# msp430.net
KiCad netlist of a schematic drawn in Altium Designer
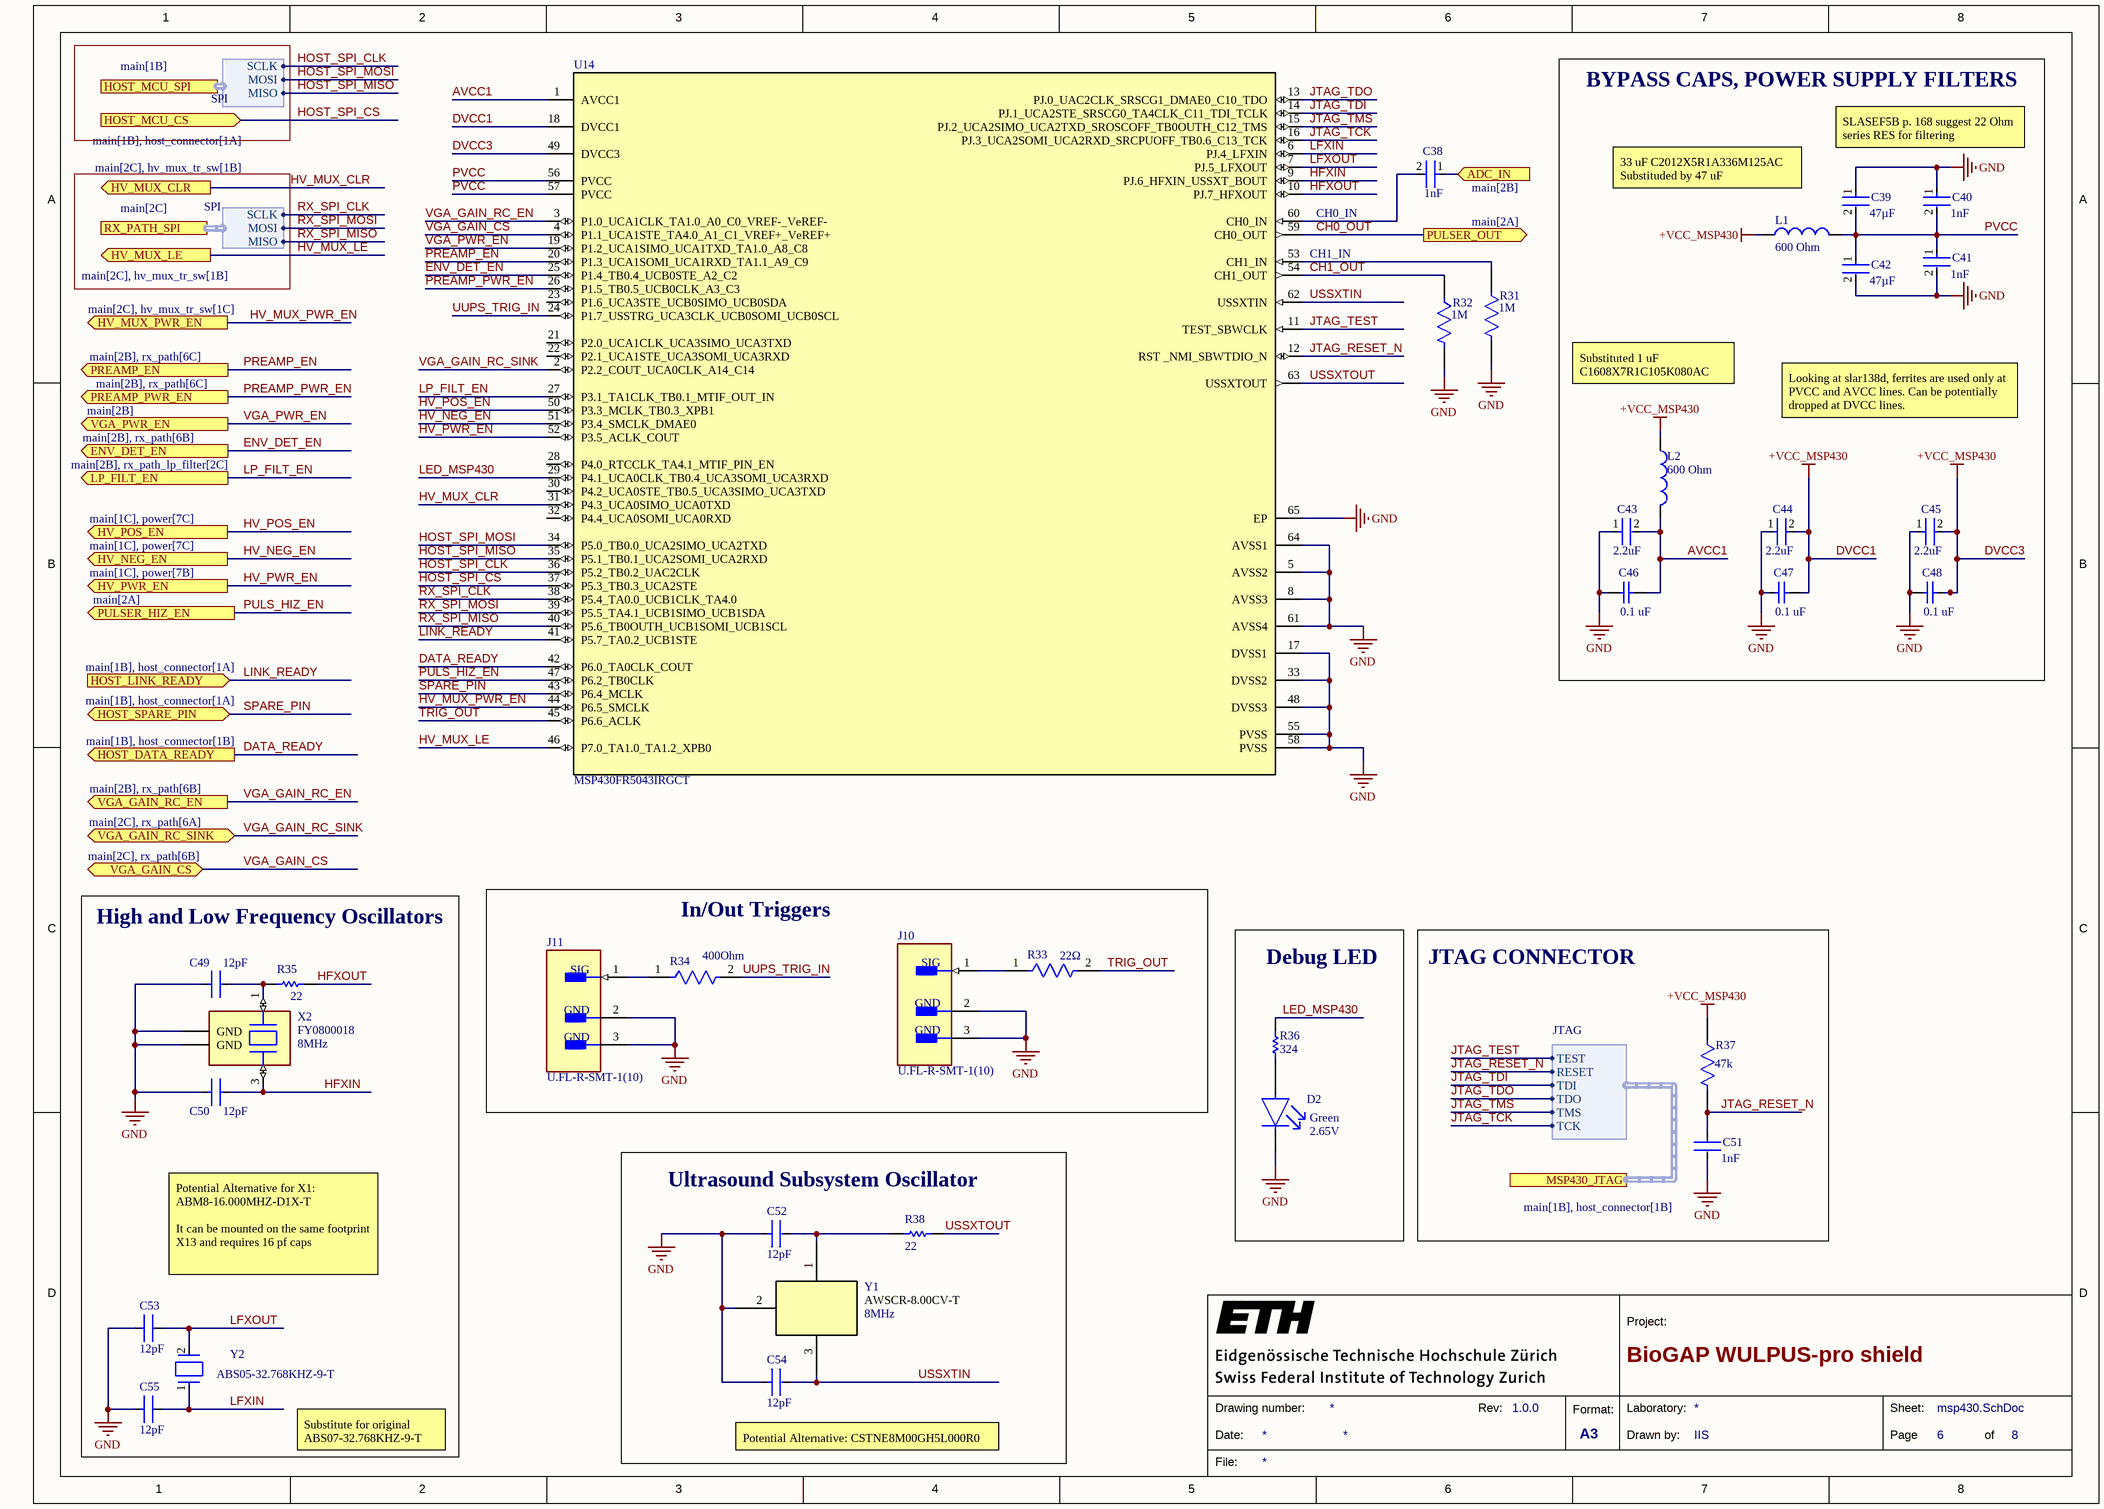
[diagram p0: msp430.SchDoc]

(export (version "E")
  (design (tool "Eeschema 10.0.6"))
  (components
    (comp (ref "C38")
      (value "GRM1555C1H102JA01D")
      (footprint "FP-GRM155-0_05-IPC_B")
      (fields
        (field (name "TOLERANCE") "5%")
        (field (name "VOLTAGE") "50V")
        (field (name "CAPACITANCE") "1nF")
      )
      (libsource (lib "") (part "02cd4be3c70576c341d710602a673aa_1"))
    )
    (comp (ref "C39")
      (value "GRM188R60J476ME01D")
      (footprint "FP-GRM188-0_2-MFG")
      (fields (field (name "TOLERANCE") "20%") (field (name "CAPACITANCE") "47µF"))
      (libsource (lib "Altium Content Vault") (part "b4654b650e69147ec39a6b967a45e02"))
    )
    (comp (ref "C40")
      (value "GRM1555C1H102JA01D")
      (footprint "FP-GRM155-0_05-IPC_B")
      (fields
        (field (name "TOLERANCE") "5%")
        (field (name "VOLTAGE") "50V")
        (field (name "CAPACITANCE") "1nF")
      )
      (libsource (lib "") (part "02cd4be3c70576c341d710602a673aa_1"))
    )
    (comp (ref "C41")
      (value "GRM1555C1H102JA01D")
      (footprint "FP-GRM155-0_05-IPC_B")
      (fields
        (field (name "TOLERANCE") "5%")
        (field (name "VOLTAGE") "50V")
        (field (name "CAPACITANCE") "1nF")
      )
      (libsource (lib "") (part "02cd4be3c70576c341d710602a673aa_1"))
    )
    (comp (ref "C42")
      (value "GRM188R60J476ME01D")
      (footprint "FP-GRM188-0_2-MFG")
      (fields (field (name "TOLERANCE") "20%") (field (name "CAPACITANCE") "47µF"))
      (libsource (lib "Altium Content Vault") (part "b4654b650e69147ec39a6b967a45e02"))
    )
    (comp (ref "C43")
      (value "C1005X7S1A225K050BC")
      (footprint "FP-C1005-050-0_15-0_1-MFG")
      (fields (field (name "CAPACITANCE") "2.2uF") (field (name "TOLERANCE") "10%"))
      (libsource (lib "Altium Content Vault") (part "b4654b650e69147ec39a6b967a45e02"))
    )
    (comp (ref "C44")
      (value "C1005X7S1A225K050BC")
      (footprint "FP-C1005-050-0_15-0_1-MFG")
      (fields (field (name "CAPACITANCE") "2.2uF") (field (name "TOLERANCE") "10%"))
      (libsource (lib "Altium Content Vault") (part "b4654b650e69147ec39a6b967a45e02"))
    )
    (comp (ref "C45")
      (value "C1005X7S1A225K050BC")
      (footprint "FP-C1005-050-0_15-0_1-MFG")
      (fields (field (name "CAPACITANCE") "2.2uF") (field (name "TOLERANCE") "10%"))
      (libsource (lib "Altium Content Vault") (part "b4654b650e69147ec39a6b967a45e02"))
    )
    (comp (ref "C46")
      (value "C0402C104K4RACTU")
      (footprint "CAPC1005X55X30LL05T10")
      (fields (field (name "MANUFACTURER") "Kemet") (field (name "CAPACITANCE") "0.1 uF"))
      (libsource (lib "Altium Content Vault") (part "CAP"))
    )
    (comp (ref "C47")
      (value "C0402C104K4RACTU")
      (footprint "CAPC1005X55X30LL05T10")
      (fields (field (name "MANUFACTURER") "Kemet") (field (name "CAPACITANCE") "0.1 uF"))
      (libsource (lib "Altium Content Vault") (part "CAP"))
    )
    (comp (ref "C48")
      (value "C0402C104K4RACTU")
      (footprint "CAPC1005X55X30LL05T10")
      (fields (field (name "MANUFACTURER") "Kemet") (field (name "CAPACITANCE") "0.1 uF"))
      (libsource (lib "Altium Content Vault") (part "CAP"))
    )
    (comp (ref "C49")
      (value "GJM1555C1H120GB01D")
      (footprint "FP-GJM155-0_05-IPC_A")
      (description "Multi-Layer Ceramic Capacitor 12pF C0G  ±2% 0402 Paper T/R")
      (fields (field (name "TOLERANCE") "2%") (field (name "CAPACITANCE") "12pF"))
      (libsource (lib "Altium Content Vault") (part "02cd4be3c70576c341d710602a673aa"))
    )
    (comp (ref "C50")
      (value "GJM1555C1H120GB01D")
      (footprint "FP-GJM155-0_05-IPC_A")
      (description "Multi-Layer Ceramic Capacitor 12pF C0G  ±2% 0402 Paper T/R")
      (fields (field (name "TOLERANCE") "2%") (field (name "CAPACITANCE") "12pF"))
      (libsource (lib "Altium Content Vault") (part "02cd4be3c70576c341d710602a673aa"))
    )
    (comp (ref "C51")
      (value "GRM1555C1H102JA01D")
      (footprint "FP-GRM155-0_05-IPC_B")
      (description "Chip Multilayer Ceramic Capacitors for General Purpose, 0402, 1000pF, C0G, 30ppm/°C, 5%, 50V")
      (fields
        (field (name "TOLERANCE") "5%")
        (field (name "VOLTAGE") "50V")
        (field (name "CAPACITANCE") "1nF")
      )
      (libsource (lib "Altium Content Vault") (part "02cd4be3c70576c341d710602a673aa"))
    )
    (comp (ref "C52")
      (value "GJM1555C1H120GB01D")
      (footprint "FP-GJM155-0_05-IPC_A")
      (description "Multi-Layer Ceramic Capacitor 12pF C0G  ±2% 0402 Paper T/R")
      (fields (field (name "TOLERANCE") "2%") (field (name "CAPACITANCE") "12pF"))
      (libsource (lib "Altium Content Vault") (part "02cd4be3c70576c341d710602a673aa"))
    )
    (comp (ref "C53")
      (value "GJM1555C1H120GB01D")
      (footprint "FP-GJM155-0_05-IPC_A")
      (description "Multi-Layer Ceramic Capacitor 12pF C0G  ±2% 0402 Paper T/R")
      (fields (field (name "TOLERANCE") "2%") (field (name "CAPACITANCE") "12pF"))
      (libsource (lib "Altium Content Vault") (part "02cd4be3c70576c341d710602a673aa"))
    )
    (comp (ref "C54")
      (value "GJM1555C1H120GB01D")
      (footprint "FP-GJM155-0_05-IPC_A")
      (description "Multi-Layer Ceramic Capacitor 12pF C0G  ±2% 0402 Paper T/R")
      (fields (field (name "TOLERANCE") "2%") (field (name "CAPACITANCE") "12pF"))
      (libsource (lib "Altium Content Vault") (part "02cd4be3c70576c341d710602a673aa"))
    )
    (comp (ref "C55")
      (value "GJM1555C1H120GB01D")
      (footprint "FP-GJM155-0_05-IPC_A")
      (description "Multi-Layer Ceramic Capacitor 12pF C0G  ±2% 0402 Paper T/R")
      (fields (field (name "TOLERANCE") "2%") (field (name "CAPACITANCE") "12pF"))
      (libsource (lib "Altium Content Vault") (part "02cd4be3c70576c341d710602a673aa"))
    )
    (comp (ref "D2")
      (value "APHD1608LZGCK")
      (footprint "FP-APHD1608LZGCK-MFG")
      (description "LED GREEN CLEAR 1608 SMD")
      (fields (field (name "FORWARD VOLTAGE") "2.65V") (field (name "COLOR") "Green"))
      (libsource (lib "Altium Content Vault") (part "8706943c75ba83719d021d2fdc84c58"))
    )
    (comp (ref "J10")
      (value "U.FL-R-SMT-1(10)")
      (footprint "FP-U_FL-R-SMT-1_10-MFG")
      (description "CONN U.FL RCPT STR 50 OHM SMD")
      (libsource (lib "Altium Content Vault") (part "7158abf7d987fa84906f6fb0d115710"))
    )
    (comp (ref "J11")
      (value "U.FL-R-SMT-1(10)")
      (footprint "FP-U_FL-R-SMT-1_10-MFG")
      (description "CONN U.FL RCPT STR 50 OHM SMD")
      (libsource (lib "Altium Content Vault") (part "7158abf7d987fa84906f6fb0d115710"))
    )
    (comp (ref "L1")
      (value "742792040")
      (footprint "SMD-0805")
      (description "SMD EMI Suppression Ferrite Bead WE-CBF, Z = 600 Ohm")
      (fields (field (name "IMPEDANCE") "600 Ohm"))
      (libsource (lib "Altium Content Vault") (part "PAS-IND-INDUCTOR-2"))
    )
    (comp (ref "L2")
      (value "742792040")
      (footprint "SMD-0805")
      (description "SMD EMI Suppression Ferrite Bead WE-CBF, Z = 600 Ohm")
      (fields (field (name "IMPEDANCE") "600 Ohm"))
      (libsource (lib "Altium Content Vault") (part "PAS-IND-INDUCTOR-2"))
    )
    (comp (ref "R31")
      (value "CRCW04021M00FKED")
      (footprint "FP-CRCW0402-e3-MFG")
      (description "RES Thick Film, 1MΩ, 1%, 0.063W, 100ppm/°C, 0402")
      (fields (field (name "TOLERANCE") "1%") (field (name "RESISTANCE") "1M"))
      (libsource (lib "") (part "1029c3af85768c4190bb7ad29bc67b5_1"))
    )
    (comp (ref "R32")
      (value "CRCW04021M00FKED")
      (footprint "FP-CRCW0402-e3-MFG")
      (description "RES Thick Film, 1MΩ, 1%, 0.063W, 100ppm/°C, 0402")
      (fields (field (name "TOLERANCE") "1%") (field (name "RESISTANCE") "1M"))
      (libsource (lib "") (part "1029c3af85768c4190bb7ad29bc67b5_1"))
    )
    (comp (ref "R33")
      (value "RC0402JR-0722RL")
      (footprint "FP-CRCW0402-C-e3-MFG")
      (fields (field (name "RESISTANCE") "22Ω") (field (name "TOLERANCE") "1%"))
      (libsource (lib "Altium Content Vault") (part "1029c3af85768c4190bb7ad29bc67b5"))
    )
    (comp (ref "R34")
      (value "CRCW0402402RFKEDC")
      (footprint "FP-CRCW0402-C-e3-MFG")
      (fields (field (name "RESISTANCE") "400Ohm") (field (name "TOLERANCE") "1%"))
      (libsource (lib "Altium Content Vault") (part "1029c3af85768c4190bb7ad29bc67b5"))
    )
    (comp (ref "R35")
      (value "RC0402JR-0722RL")
      (footprint "RESC1005X40X25NL05T10")
      (fields (field (name "MANUFACTURER") "Yageo / Phycomp") (field (name "RESISTANCE") "22"))
      (libsource (lib "Altium Content Vault") (part "RES"))
    )
    (comp (ref "R36")
      (value "CPF0402B324RE1")
      (footprint "RESC1005X35X20ML05T10")
      (fields (field (name "MANUFACTURER") "TE Connectivity / AMP") (field (name "RESISTANCE") "324"))
      (libsource (lib "Altium Content Vault") (part "RES"))
    )
    (comp (ref "R37")
      (value "CRCW040247K0FKED")
      (footprint "FP-CRCW0402-e3-IPC_C")
      (description "RES Thick Film, 47kΩ, 1%, 0.063W, 100ppm/°C, 0402")
      (fields (field (name "TOLERANCE") "1%") (field (name "RESISTANCE") "47k"))
      (libsource (lib "") (part "1029c3af85768c4190bb7ad29bc67b5_1"))
    )
    (comp (ref "R38")
      (value "RC0402JR-0722RL")
      (footprint "RESC1005X40X25NL05T10")
      (fields (field (name "MANUFACTURER") "Yageo / Phycomp") (field (name "RESISTANCE") "22"))
      (libsource (lib "Altium Content Vault") (part "RES"))
    )
    (comp (ref "U14")
      (value "MSP430FR5043IRGCT")
      (footprint "RGC0064G")
      (description "No Description Available")
      (fields (field (name "COPYRIGHT") "Copyright (C) 2021 Ultra Librarian. All rights reserved."))
      (libsource (lib "Schlib1") (part "MSP430FR5043IRGCT"))
    )
    (comp (ref "X2")
      (value "FY0800018")
      (footprint "XTAL_ECS-80-18-30B-AGN-TR")
      (description "Crystal 8MHz ±30ppm (Tol) ±30ppm (Stability) 18pF FUND 100Ohm 4-Pin SMD T/R")
      (fields (field (name "MANUFACTURER") "Diodes") (field (name "FREQUENCY") "8MHz"))
      (libsource (lib "Schlib1") (part "FY0800018"))
    )
    (comp (ref "Y1")
      (value "AWSCR-8.00CV-T")
      (footprint "AWSCR-8.00CV-T_ABR")
      (description "No Description Available")
      (fields
        (field (name "MANUFACTURER_PART_NUMBER") "AWSCR-8.00CV-T")
        (field (name "FREQUENCY") "8MHz")
        (field (name "COPYRIGHT") "Copyright (C) 2021 Ultra Librarian. All rights reserved.")
      )
      (libsource (lib "Schlib1") (part "AWSCR-8.00CV-T"))
    )
    (comp (ref "Y2")
      (value "ABS05-32.768KHZ-9-T")
      (footprint "FP-ABS05-MFG")
      (description "CRYSTAL 32.7680KHZ 9PF SMD")
      (fields (field (name "TOLERANCE") "20ppm"))
      (libsource (lib "Altium Content Vault") (part "c23a69dc6c9e2f18f2079038eb95dd1"))
    )
  )
  (nets
    (net (code "3") (name "+VCC_MSP430") (class "Default")
      (node (ref "C44") (pin "2") (pinfunction "2_2") (pintype "passive"))
      (node (ref "C45") (pin "2") (pinfunction "2_2") (pintype "passive"))
      (node (ref "C47") (pin "1") (pinfunction "1_1") (pintype "passive"))
      (node (ref "C48") (pin "1") (pinfunction "1_1") (pintype "passive"))
      (node (ref "L1") (pin "1") (pinfunction "1_1") (pintype "passive"))
      (node (ref "L2") (pin "1") (pinfunction "1_1") (pintype "passive"))
      (node (ref "R37") (pin "1") (pinfunction "1_1") (pintype "passive"))
      (node (ref "U14") (pin "18") (pinfunction "DVCC1_18") (pintype "power_in"))
      (node (ref "U14") (pin "49") (pinfunction "DVCC3_49") (pintype "power_in"))
    )
    (net (code "4") (name "/ADC_IN") (class "Default")
      (node (ref "C38") (pin "1") (pinfunction "1_1") (pintype "passive"))
    )
    (net (code "5") (name "/AVCC1") (class "Default")
      (node (ref "C43") (pin "2") (pinfunction "2_2") (pintype "passive"))
      (node (ref "C46") (pin "1") (pinfunction "1_1") (pintype "passive"))
      (node (ref "L2") (pin "2") (pinfunction "2_2") (pintype "passive"))
      (node (ref "U14") (pin "1") (pinfunction "AVCC1_1") (pintype "power_in"))
    )
    (net (code "6") (name "/CH0_OUT") (class "Default")
      (node (ref "U14") (pin "59") (pinfunction "CH0_OUT_59") (pintype "output"))
    )
    (net (code "7") (name "/CH1_OUT") (class "Default")
      (node (ref "R32") (pin "1") (pinfunction "1_1") (pintype "passive"))
      (node (ref "U14") (pin "54") (pinfunction "CH1_OUT_54") (pintype "output"))
    )
    (net (code "8") (name "/DATA_READY") (class "Default")
      (node (ref "U14") (pin "42") (pinfunction "P6.0_TA0CLK_COUT_42") (pintype "bidirectional"))
    )
    (net (code "9") (name "/ENV_DET_EN") (class "Default")
      (node (ref "U14") (pin "25") (pinfunction "P1.4_TB0.4_UCB0STE_A2_C2_25") (pintype "bidirectional"))
    )
    (net (code "10") (name "/HFXIN") (class "Default")
      (node (ref "C50") (pin "2") (pinfunction "2_2") (pintype "passive"))
      (node (ref "U14") (pin "9") (pinfunction "PJ.6_HFXIN_USSXT_BOUT_9") (pintype "bidirectional"))
      (node (ref "X2") (pin "3") (pinfunction "OUT/IN_3") (pintype "bidirectional"))
    )
    (net (code "11") (name "/HFXOUT") (class "Default")
      (node (ref "R35") (pin "2") (pinfunction "2_2") (pintype "passive"))
      (node (ref "U14") (pin "10") (pinfunction "PJ.7_HFXOUT_10") (pintype "bidirectional"))
    )
    (net (code "12") (name "/HOST_SPI_CLK") (class "Default")
      (node (ref "U14") (pin "36") (pinfunction "P5.2_TB0.2_UAC2CLK_36") (pintype "bidirectional"))
    )
    (net (code "13") (name "/HOST_SPI_CS") (class "Default")
      (node (ref "U14") (pin "37") (pinfunction "P5.3_TB0.3_UCA2STE_37") (pintype "bidirectional"))
    )
    (net (code "14") (name "/HOST_SPI_MISO") (class "Default")
      (node (ref "U14") (pin "35") (pinfunction "P5.1_TB0.1_UCA2SOMI_UCA2RXD_35") (pintype "bidirectional"))
    )
    (net (code "15") (name "/HOST_SPI_MOSI") (class "Default")
      (node (ref "U14") (pin "34") (pinfunction "P5.0_TB0.0_UCA2SIMO_UCA2TXD_34") (pintype "bidirectional"))
    )
    (net (code "16") (name "/HV_MUX_CLR") (class "Default")
      (node (ref "U14") (pin "31") (pinfunction "P4.3_UCA0SIMO_UCA0TXD_31") (pintype "bidirectional"))
    )
    (net (code "17") (name "/HV_MUX_LE") (class "Default")
      (node (ref "U14") (pin "46") (pinfunction "P7.0_TA1.0_TA1.2_XPB0_46") (pintype "bidirectional"))
    )
    (net (code "18") (name "/HV_MUX_PWR_EN") (class "Default")
      (node (ref "U14") (pin "44") (pinfunction "P6.5_SMCLK_44") (pintype "bidirectional"))
    )
    (net (code "19") (name "/HV_NEG_EN") (class "Default")
      (node (ref "U14") (pin "51") (pinfunction "P3.4_SMCLK_DMAE0_51") (pintype "bidirectional"))
    )
    (net (code "20") (name "/HV_POS_EN") (class "Default")
      (node (ref "U14") (pin "50") (pinfunction "P3.3_MCLK_TB0.3_XPB1_50") (pintype "bidirectional"))
    )
    (net (code "21") (name "/HV_PWR_EN") (class "Default")
      (node (ref "U14") (pin "52") (pinfunction "P3.5_ACLK_COUT_52") (pintype "bidirectional"))
    )
    (net (code "22") (name "/JTAG_RESET_N") (class "Default")
      (node (ref "C51") (pin "1") (pinfunction "1_1") (pintype "passive"))
      (node (ref "R37") (pin "2") (pinfunction "2_2") (pintype "passive"))
      (node (ref "U14") (pin "12") (pinfunction "RST__NMI_SBWTDIO_N_12") (pintype "bidirectional"))
    )
    (net (code "23") (name "/JTAG_TCK") (class "Default")
      (node (ref "U14") (pin "16") (pinfunction "PJ.3_UCA2SOMI_UCA2RXD_SRCPUOFF_TB0.6_C13_TCK_16") (pintype "bidirectional"))
    )
    (net (code "24") (name "/JTAG_TDI") (class "Default")
      (node (ref "U14") (pin "14") (pinfunction "PJ.1_UCA2STE_SRSCG0_TA4CLK_C11_TDI_TCLK_14") (pintype "bidirectional"))
    )
    (net (code "25") (name "/JTAG_TDO") (class "Default")
      (node (ref "U14") (pin "13") (pinfunction "PJ.0_UAC2CLK_SRSCG1_DMAE0_C10_TDO_13") (pintype "bidirectional"))
    )
    (net (code "26") (name "/JTAG_TEST") (class "Default")
      (node (ref "U14") (pin "11") (pinfunction "TEST_SBWCLK_11") (pintype "input"))
    )
    (net (code "27") (name "/JTAG_TMS") (class "Default")
      (node (ref "U14") (pin "15") (pinfunction "PJ.2_UCA2SIMO_UCA2TXD_SROSCOFF_TB0OUTH_C12_TMS_15") (pintype "bidirectional"))
    )
    (net (code "28") (name "/LED_MSP430") (class "Default")
      (node (ref "R36") (pin "1") (pinfunction "1_1") (pintype "passive"))
      (node (ref "U14") (pin "29") (pinfunction "P4.1_UCA0CLK_TB0.4_UCA3SOMI_UCA3RXD_29") (pintype "bidirectional"))
    )
    (net (code "29") (name "/LFXIN") (class "Default")
      (node (ref "C55") (pin "2") (pinfunction "2_2") (pintype "passive"))
      (node (ref "U14") (pin "6") (pinfunction "PJ.4_LFXIN_6") (pintype "bidirectional"))
      (node (ref "Y2") (pin "1") (pinfunction "1_1") (pintype "passive"))
    )
    (net (code "30") (name "/LFXOUT") (class "Default")
      (node (ref "C53") (pin "2") (pinfunction "2_2") (pintype "passive"))
      (node (ref "U14") (pin "7") (pinfunction "PJ.5_LFXOUT_7") (pintype "bidirectional"))
      (node (ref "Y2") (pin "2") (pinfunction "2_2") (pintype "passive"))
    )
    (net (code "31") (name "/LINK_READY") (class "Default")
      (node (ref "U14") (pin "41") (pinfunction "P5.7_TA0.2_UCB1STE_41") (pintype "bidirectional"))
    )
    (net (code "32") (name "/LP_FILT_EN") (class "Default")
      (node (ref "U14") (pin "27") (pinfunction "P3.1_TA1CLK_TB0.1_MTIF_OUT_IN_27") (pintype "bidirectional"))
    )
    (net (code "33") (name "/PREAMP_EN") (class "Default")
      (node (ref "U14") (pin "20") (pinfunction "P1.3_UCA1SOMI_UCA1RXD_TA1.1_A9_C9_20") (pintype "bidirectional"))
    )
    (net (code "34") (name "/PREAMP_PWR_EN") (class "Default")
      (node (ref "U14") (pin "26") (pinfunction "P1.5_TB0.5_UCB0CLK_A3_C3_26") (pintype "bidirectional"))
    )
    (net (code "35") (name "/PULS_HIZ_EN") (class "Default")
      (node (ref "U14") (pin "47") (pinfunction "P6.2_TB0CLK_47") (pintype "bidirectional"))
    )
    (net (code "36") (name "/PVCC") (class "Default")
      (node (ref "C39") (pin "2") (pinfunction "2_2") (pintype "passive"))
      (node (ref "C40") (pin "2") (pinfunction "2_2") (pintype "passive"))
      (node (ref "C41") (pin "1") (pinfunction "1_1") (pintype "passive"))
      (node (ref "C42") (pin "1") (pinfunction "1_1") (pintype "passive"))
      (node (ref "L1") (pin "2") (pinfunction "2_2") (pintype "passive"))
      (node (ref "U14") (pin "56") (pinfunction "PVCC_56") (pintype "power_in"))
      (node (ref "U14") (pin "57") (pinfunction "PVCC_57") (pintype "power_in"))
    )
    (net (code "37") (name "/RX_SPI_CLK") (class "Default")
      (node (ref "U14") (pin "38") (pinfunction "P5.4_TA0.0_UCB1CLK_TA4.0_38") (pintype "bidirectional"))
    )
    (net (code "38") (name "/RX_SPI_MISO") (class "Default")
      (node (ref "U14") (pin "40") (pinfunction "P5.6_TB0OUTH_UCB1SOMI_UCB1SCL_40") (pintype "bidirectional"))
    )
    (net (code "39") (name "/RX_SPI_MOSI") (class "Default")
      (node (ref "U14") (pin "39") (pinfunction "P5.5_TA4.1_UCB1SIMO_UCB1SDA_39") (pintype "bidirectional"))
    )
    (net (code "40") (name "/SPARE_PIN") (class "Default")
      (node (ref "U14") (pin "43") (pinfunction "P6.4_MCLK_43") (pintype "bidirectional"))
    )
    (net (code "41") (name "/TRIG_OUT") (class "Default")
      (node (ref "R33") (pin "2") (pinfunction "2_2") (pintype "passive"))
      (node (ref "U14") (pin "45") (pinfunction "P6.6_ACLK_45") (pintype "bidirectional"))
    )
    (net (code "42") (name "/USSXTIN") (class "Default")
      (node (ref "C54") (pin "2") (pinfunction "2_2") (pintype "passive"))
      (node (ref "U14") (pin "62") (pinfunction "USSXTIN_62") (pintype "input"))
      (node (ref "Y1") (pin "3") (pinfunction "3_3") (pintype "passive"))
    )
    (net (code "43") (name "/USSXTOUT") (class "Default")
      (node (ref "R38") (pin "2") (pinfunction "2_2") (pintype "passive"))
      (node (ref "U14") (pin "63") (pinfunction "USSXTOUT_63") (pintype "output"))
    )
    (net (code "44") (name "/UUPS_TRIG_IN") (class "Default")
      (node (ref "R34") (pin "2") (pinfunction "2_2") (pintype "passive"))
      (node (ref "U14") (pin "24") (pinfunction "P1.7_USSTRG_UCA3CLK_UCB0SOMI_UCB0SCL_24") (pintype "bidirectional"))
    )
    (net (code "45") (name "/VGA_GAIN_CS") (class "Default")
      (node (ref "U14") (pin "4") (pinfunction "P1.1_UCA1STE_TA4.0_A1_C1_VREF+_VeREF+_4") (pintype "bidirectional"))
    )
    (net (code "46") (name "/VGA_GAIN_RC_EN") (class "Default")
      (node (ref "U14") (pin "3") (pinfunction "P1.0_UCA1CLK_TA1.0_A0_C0_VREF-_VeREF-_3") (pintype "bidirectional"))
    )
    (net (code "47") (name "/VGA_GAIN_RC_SINK") (class "Default")
      (node (ref "U14") (pin "2") (pinfunction "P2.2_COUT_UCA0CLK_A14_C14_2") (pintype "bidirectional"))
    )
    (net (code "48") (name "/VGA_PWR_EN") (class "Default")
      (node (ref "U14") (pin "19") (pinfunction "P1.2_UCA1SIMO_UCA1TXD_TA1.0_A8_C8_19") (pintype "bidirectional"))
    )
    (net (code "51") (name "GND") (class "Default")
      (node (ref "C39") (pin "1") (pinfunction "1_1") (pintype "passive"))
      (node (ref "C40") (pin "1") (pinfunction "1_1") (pintype "passive"))
      (node (ref "C41") (pin "2") (pinfunction "2_2") (pintype "passive"))
      (node (ref "C42") (pin "2") (pinfunction "2_2") (pintype "passive"))
      (node (ref "C43") (pin "1") (pinfunction "1_1") (pintype "passive"))
      (node (ref "C44") (pin "1") (pinfunction "1_1") (pintype "passive"))
      (node (ref "C45") (pin "1") (pinfunction "1_1") (pintype "passive"))
      (node (ref "C46") (pin "2") (pinfunction "2_2") (pintype "passive"))
      (node (ref "C47") (pin "2") (pinfunction "2_2") (pintype "passive"))
      (node (ref "C48") (pin "2") (pinfunction "2_2") (pintype "passive"))
      (node (ref "C49") (pin "1") (pinfunction "1_1") (pintype "passive"))
      (node (ref "C50") (pin "1") (pinfunction "1_1") (pintype "passive"))
      (node (ref "C51") (pin "2") (pinfunction "2_2") (pintype "passive"))
      (node (ref "C52") (pin "1") (pinfunction "1_1") (pintype "passive"))
      (node (ref "C53") (pin "1") (pinfunction "1_1") (pintype "passive"))
      (node (ref "C54") (pin "1") (pinfunction "1_1") (pintype "passive"))
      (node (ref "C55") (pin "1") (pinfunction "1_1") (pintype "passive"))
      (node (ref "D2") (pin "1") (pinfunction "C_1") (pintype "passive"))
      (node (ref "J10") (pin "2") (pinfunction "GND_2") (pintype "power_in"))
      (node (ref "J10") (pin "3") (pinfunction "GND_3") (pintype "power_in"))
      (node (ref "J11") (pin "2") (pinfunction "GND_2") (pintype "power_in"))
      (node (ref "J11") (pin "3") (pinfunction "GND_3") (pintype "power_in"))
      (node (ref "R31") (pin "2") (pinfunction "2_2") (pintype "passive"))
      (node (ref "R32") (pin "2") (pinfunction "2_2") (pintype "passive"))
      (node (ref "U14") (pin "17") (pinfunction "DVSS1_17") (pintype "power_in"))
      (node (ref "U14") (pin "33") (pinfunction "DVSS2_33") (pintype "power_in"))
      (node (ref "U14") (pin "48") (pinfunction "DVSS3_48") (pintype "power_in"))
      (node (ref "U14") (pin "5") (pinfunction "AVSS2_5") (pintype "power_in"))
      (node (ref "U14") (pin "55") (pinfunction "PVSS_55") (pintype "power_in"))
      (node (ref "U14") (pin "58") (pinfunction "PVSS_58") (pintype "power_in"))
      (node (ref "U14") (pin "61") (pinfunction "AVSS4_61") (pintype "power_in"))
      (node (ref "U14") (pin "64") (pinfunction "AVSS1_64") (pintype "power_in"))
      (node (ref "U14") (pin "65") (pinfunction "EP_65") (pintype "passive"))
      (node (ref "U14") (pin "8") (pinfunction "AVSS3_8") (pintype "power_in"))
      (node (ref "X2") (pin "2") (pinfunction "GND_2") (pintype "power_in"))
      (node (ref "X2") (pin "4") (pinfunction "GND_4") (pintype "power_in"))
      (node (ref "Y1") (pin "2") (pinfunction "2_2") (pintype "passive"))
    )
    (net (code "52") (name "Net-(C52-Pad2)") (class "Default")
      (node (ref "C52") (pin "2") (pinfunction "2_2") (pintype "passive"))
      (node (ref "R38") (pin "1") (pinfunction "1_1") (pintype "passive"))
      (node (ref "Y1") (pin "1") (pinfunction "1_1") (pintype "passive"))
    )
    (net (code "53") (name "Net-(D2-A)") (class "Default")
      (node (ref "D2") (pin "2") (pinfunction "A_2") (pintype "passive"))
      (node (ref "R36") (pin "2") (pinfunction "2_2") (pintype "passive"))
    )
    (net (code "54") (name "Net-(J10-SIG)") (class "Default")
      (node (ref "J10") (pin "1") (pinfunction "SIG_1") (pintype "input"))
      (node (ref "R33") (pin "1") (pinfunction "1_1") (pintype "passive"))
    )
    (net (code "55") (name "Net-(J11-SIG)") (class "Default")
      (node (ref "J11") (pin "1") (pinfunction "SIG_1") (pintype "input"))
      (node (ref "R34") (pin "1") (pinfunction "1_1") (pintype "passive"))
    )
    (net (code "56") (name "Net-(U14-CH0_IN)") (class "Default")
      (node (ref "C38") (pin "2") (pinfunction "2_2") (pintype "passive"))
      (node (ref "U14") (pin "60") (pinfunction "CH0_IN_60") (pintype "input"))
    )
    (net (code "57") (name "Net-(U14-CH1_IN)") (class "Default")
      (node (ref "R31") (pin "1") (pinfunction "1_1") (pintype "passive"))
      (node (ref "U14") (pin "53") (pinfunction "CH1_IN_53") (pintype "input"))
    )
    (net (code "58") (name "Net-(X2-IN{slash}OUT)") (class "Default")
      (node (ref "C49") (pin "2") (pinfunction "2_2") (pintype "passive"))
      (node (ref "R35") (pin "1") (pinfunction "1_1") (pintype "passive"))
      (node (ref "X2") (pin "1") (pinfunction "IN/OUT_1") (pintype "bidirectional"))
    )
    (net (code "59") (name "unconnected-(U14-P1.6_UCA3STE_UCB0SIMO_UCB0SDA-Pad23)") (class "Default")
      (node (ref "U14") (pin "23") (pinfunction "P1.6_UCA3STE_UCB0SIMO_UCB0SDA_23") (pintype "bidirectional"))
    )
    (net (code "60") (name "unconnected-(U14-P2.0_UCA1CLK_UCA3SIMO_UCA3TXD-Pad21)") (class "Default")
      (node (ref "U14") (pin "21") (pinfunction "P2.0_UCA1CLK_UCA3SIMO_UCA3TXD_21") (pintype "bidirectional"))
    )
    (net (code "61") (name "unconnected-(U14-P2.1_UCA1STE_UCA3SOMI_UCA3RXD-Pad22)") (class "Default")
      (node (ref "U14") (pin "22") (pinfunction "P2.1_UCA1STE_UCA3SOMI_UCA3RXD_22") (pintype "bidirectional"))
    )
    (net (code "62") (name "unconnected-(U14-P4.0_RTCCLK_TA4.1_MTIF_PIN_EN-Pad28)") (class "Default")
      (node (ref "U14") (pin "28") (pinfunction "P4.0_RTCCLK_TA4.1_MTIF_PIN_EN_28") (pintype "bidirectional"))
    )
    (net (code "63") (name "unconnected-(U14-P4.2_UCA0STE_TB0.5_UCA3SIMO_UCA3TXD-Pad30)") (class "Default")
      (node (ref "U14") (pin "30") (pinfunction "P4.2_UCA0STE_TB0.5_UCA3SIMO_UCA3TXD_30") (pintype "bidirectional"))
    )
    (net (code "64") (name "unconnected-(U14-P4.4_UCA0SOMI_UCA0RXD-Pad32)") (class "Default")
      (node (ref "U14") (pin "32") (pinfunction "P4.4_UCA0SOMI_UCA0RXD_32") (pintype "bidirectional"))
    )
  )
)
